# Amplificador_Push_Pull_AB.net
KiCad netlist of a schematic drawn in EAGLE
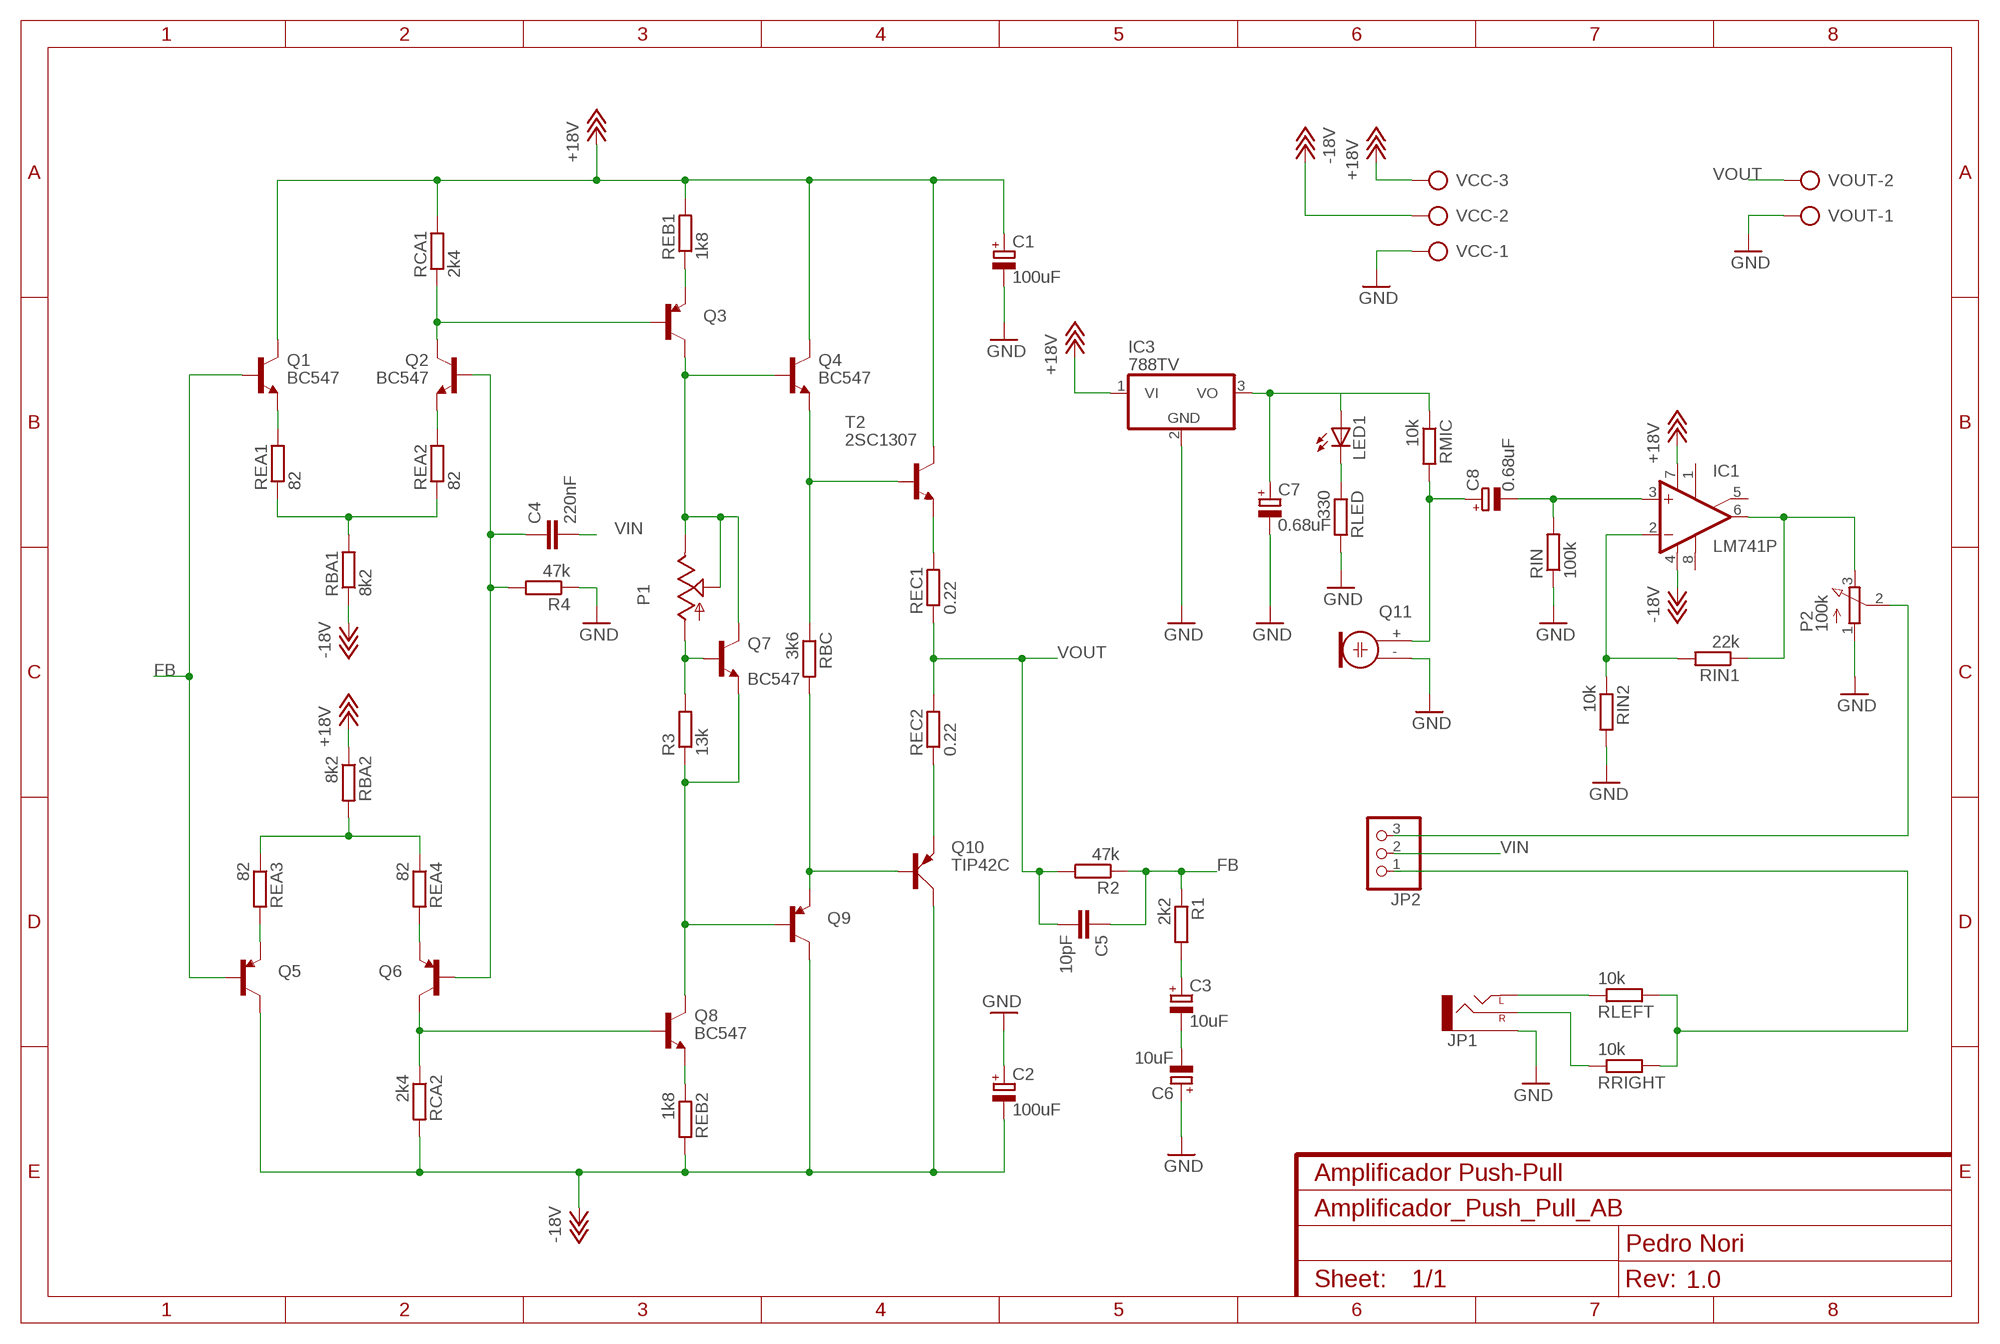
[diagram p0: schematic, sheet 1]

(export (version "E")
  (design (tool "Eeschema 10.0.6"))
  (components
    (comp (ref "C1")
      (value "100uF")
      (footprint "eagle-import:E2,5-6")
      (libsource (lib "eagle-import") (part "CPOL-EUE2.5-6"))
    )
    (comp (ref "C2")
      (value "100uF")
      (footprint "eagle-import:E2,5-6")
      (libsource (lib "eagle-import") (part "CPOL-EUE2.5-6"))
    )
    (comp (ref "C3")
      (value "10uF")
      (footprint "eagle-import:E2,5-5")
      (libsource (lib "eagle-import") (part "CPOL-EUE2.5-5"))
    )
    (comp (ref "C4")
      (value "220nF")
      (footprint "eagle-import:C025-025X050")
      (libsource (lib "eagle-import") (part "C-EU025-025X050"))
    )
    (comp (ref "C5")
      (value "10pF")
      (footprint "eagle-import:C025-025X050")
      (libsource (lib "eagle-import") (part "C-EU025-025X050"))
    )
    (comp (ref "C6")
      (value "10uF")
      (footprint "eagle-import:E2,5-5")
      (libsource (lib "eagle-import") (part "CPOL-EUE2.5-5"))
    )
    (comp (ref "C7")
      (value "0.68uF")
      (footprint "eagle-import:E2,5-5")
      (libsource (lib "eagle-import") (part "CPOL-EUE2.5-5"))
    )
    (comp (ref "C8")
      (value "0.68uF")
      (footprint "eagle-import:E2,5-5")
      (libsource (lib "eagle-import") (part "CPOL-EUE2.5-5"))
    )
    (comp (ref "IC1")
      (value "LM741P")
      (footprint "eagle-import:DIL08")
      (libsource (lib "eagle-import") (part "741PLM"))
    )
    (comp (ref "IC3")
      (value "788TV")
      (footprint "eagle-import:TO220V")
      (libsource (lib "eagle-import") (part "78TV8"))
    )
    (comp (ref "JP1")
      (value "AUDIO-JACKPTH")
      (footprint "eagle-import:AUDIO-JACK")
      (libsource (lib "eagle-import") (part "AUDIO-JACKPTH"))
    )
    (comp (ref "JP2")
      (value "PINHD-1X3")
      (footprint "eagle-import:1X03")
      (libsource (lib "eagle-import") (part "PINHD-1X3"))
    )
    (comp (ref "LED1")
      (value "LED5MM")
      (footprint "eagle-import:LED5MM")
      (libsource (lib "eagle-import") (part "LED5MM"))
    )
    (comp (ref "P1")
      (value "TRIM_US-S64W")
      (footprint "eagle-import:S64W")
      (libsource (lib "eagle-import") (part "TRIM_US-S64W"))
    )
    (comp (ref "P2")
      (value "100k")
      (footprint "eagle-import:3RP_1610N")
      (libsource (lib "eagle-import") (part "3RP/1610N"))
    )
    (comp (ref "Q1")
      (value "BC547")
      (footprint "eagle-import:TO92")
      (libsource (lib "eagle-import") (part "BC547"))
    )
    (comp (ref "Q2")
      (value "BC547")
      (footprint "eagle-import:TO92")
      (libsource (lib "eagle-import") (part "BC547"))
    )
    (comp (ref "Q3")
      (value "TRANSISTOR_PNPTO92")
      (footprint "eagle-import:TO-92")
      (libsource (lib "eagle-import") (part "TRANSISTOR_PNPTO92"))
    )
    (comp (ref "Q4")
      (value "BC547")
      (footprint "eagle-import:TO92")
      (libsource (lib "eagle-import") (part "BC547"))
    )
    (comp (ref "Q5")
      (value "TRANSISTOR_PNPTO92")
      (footprint "eagle-import:TO-92")
      (libsource (lib "eagle-import") (part "TRANSISTOR_PNPTO92"))
    )
    (comp (ref "Q6")
      (value "TRANSISTOR_PNPTO92")
      (footprint "eagle-import:TO-92")
      (libsource (lib "eagle-import") (part "TRANSISTOR_PNPTO92"))
    )
    (comp (ref "Q7")
      (value "BC547")
      (footprint "eagle-import:TO92")
      (libsource (lib "eagle-import") (part "BC547"))
    )
    (comp (ref "Q8")
      (value "BC547")
      (footprint "eagle-import:TO92")
      (libsource (lib "eagle-import") (part "BC547"))
    )
    (comp (ref "Q9")
      (value "TRANSISTOR_PNPTO92")
      (footprint "eagle-import:TO-92")
      (libsource (lib "eagle-import") (part "TRANSISTOR_PNPTO92"))
    )
    (comp (ref "Q10")
      (value "TIP42C")
      (footprint "eagle-import:TO220AV")
      (libsource (lib "eagle-import") (part "TIP42C"))
    )
    (comp (ref "Q11")
      (value "ELECTRET")
      (footprint "eagle-import:9.7ELECTRET")
      (libsource (lib "eagle-import") (part "ELECTRET"))
    )
    (comp (ref "R1")
      (value "2k2")
      (footprint "eagle-import:0207_10")
      (libsource (lib "eagle-import") (part "R-EU_0207/10"))
    )
    (comp (ref "R2")
      (value "47k")
      (footprint "eagle-import:0207_10")
      (libsource (lib "eagle-import") (part "R-EU_0207/10"))
    )
    (comp (ref "R3")
      (value "13k")
      (footprint "eagle-import:0207_10")
      (libsource (lib "eagle-import") (part "R-EU_0207/10"))
    )
    (comp (ref "R4")
      (value "47k")
      (footprint "eagle-import:0207_10")
      (libsource (lib "eagle-import") (part "R-EU_0207/10"))
    )
    (comp (ref "RBA1")
      (value "8k2")
      (footprint "eagle-import:0207_10")
      (libsource (lib "eagle-import") (part "R-EU_0207/10"))
    )
    (comp (ref "RBA2")
      (value "8k2")
      (footprint "eagle-import:0207_10")
      (libsource (lib "eagle-import") (part "R-EU_0207/10"))
    )
    (comp (ref "RBC")
      (value "3k6")
      (footprint "eagle-import:0207_10")
      (libsource (lib "eagle-import") (part "R-EU_0207/10"))
    )
    (comp (ref "RCA1")
      (value "2k4")
      (footprint "eagle-import:0207_10")
      (libsource (lib "eagle-import") (part "R-EU_0207/10"))
    )
    (comp (ref "RCA2")
      (value "2k4")
      (footprint "eagle-import:0207_10")
      (libsource (lib "eagle-import") (part "R-EU_0207/10"))
    )
    (comp (ref "REA1")
      (value "82")
      (footprint "eagle-import:0207_10")
      (libsource (lib "eagle-import") (part "R-EU_0207/10"))
    )
    (comp (ref "REA2")
      (value "82")
      (footprint "eagle-import:0207_10")
      (libsource (lib "eagle-import") (part "R-EU_0207/10"))
    )
    (comp (ref "REA3")
      (value "82")
      (footprint "eagle-import:0207_10")
      (libsource (lib "eagle-import") (part "R-EU_0207/10"))
    )
    (comp (ref "REA4")
      (value "82")
      (footprint "eagle-import:0207_10")
      (libsource (lib "eagle-import") (part "R-EU_0207/10"))
    )
    (comp (ref "REB1")
      (value "1k8")
      (footprint "eagle-import:0207_10")
      (libsource (lib "eagle-import") (part "R-EU_0207/10"))
    )
    (comp (ref "REB2")
      (value "1k8")
      (footprint "eagle-import:0207_10")
      (libsource (lib "eagle-import") (part "R-EU_0207/10"))
    )
    (comp (ref "REC1")
      (value "0.22")
      (footprint "eagle-import:0617_22")
      (libsource (lib "eagle-import") (part "R-EU_0617/22"))
    )
    (comp (ref "REC2")
      (value "0.22")
      (footprint "eagle-import:0617_22")
      (libsource (lib "eagle-import") (part "R-EU_0617/22"))
    )
    (comp (ref "RIN")
      (value "100k")
      (footprint "eagle-import:0207_7")
      (libsource (lib "eagle-import") (part "R-EU_0207/7"))
    )
    (comp (ref "RIN1")
      (value "22k")
      (footprint "eagle-import:0207_7")
      (libsource (lib "eagle-import") (part "R-EU_0207/7"))
    )
    (comp (ref "RIN2")
      (value "10k")
      (footprint "eagle-import:0207_10")
      (libsource (lib "eagle-import") (part "R-EU_0207/10"))
    )
    (comp (ref "RLED")
      (value "330")
      (footprint "eagle-import:0207_7")
      (libsource (lib "eagle-import") (part "R-EU_0207/7"))
    )
    (comp (ref "RLEFT")
      (value "10k")
      (footprint "eagle-import:0207_7")
      (libsource (lib "eagle-import") (part "R-EU_0207/7"))
    )
    (comp (ref "RMIC")
      (value "10k")
      (footprint "eagle-import:0207_7")
      (libsource (lib "eagle-import") (part "R-EU_0207/7"))
    )
    (comp (ref "RRIGHT")
      (value "10k")
      (footprint "eagle-import:0207_7")
      (libsource (lib "eagle-import") (part "R-EU_0207/7"))
    )
    (comp (ref "T2")
      (value "2SC1307")
      (footprint "eagle-import:TO220AV")
      (libsource (lib "eagle-import") (part "2SC1307"))
    )
    (comp (ref "VCC")
      (value "AK500/3-H")
      (footprint "eagle-import:AK500_3-H")
      (libsource (lib "eagle-import") (part "AK500/3-H"))
    )
    (comp (ref "VOUT")
      (value "AK500/2-H")
      (footprint "eagle-import:AK500_2-H")
      (libsource (lib "eagle-import") (part "AK500/2-H"))
    )
  )
  (nets
    (net (code "1") (name "+18V") (class "Default")
      (node (ref "C1") (pin "+") (pinfunction "+_+") (pintype "passive"))
      (node (ref "IC1") (pin "7") (pinfunction "V+_7") (pintype "power_in"))
      (node (ref "IC3") (pin "1") (pinfunction "VI_1") (pintype "input"))
      (node (ref "Q1") (pin "3") (pinfunction "C_3") (pintype "passive"))
      (node (ref "Q4") (pin "3") (pinfunction "C_3") (pintype "passive"))
      (node (ref "RBA2") (pin "1") (pinfunction "1_1") (pintype "passive"))
      (node (ref "RCA1") (pin "2") (pinfunction "2_2") (pintype "passive"))
      (node (ref "REB1") (pin "2") (pinfunction "2_2") (pintype "passive"))
      (node (ref "T2") (pin "2") (pinfunction "C_2") (pintype "passive"))
      (node (ref "VCC") (pin "3") (pinfunction "KL_3") (pintype "passive"))
    )
    (net (code "2") (name "-18V") (class "Default")
      (node (ref "C2") (pin "-") (pinfunction "-_-") (pintype "passive"))
      (node (ref "IC1") (pin "4") (pinfunction "V-_4") (pintype "power_in"))
      (node (ref "Q10") (pin "C") (pinfunction "C_C") (pintype "passive"))
      (node (ref "Q5") (pin "1") (pinfunction "C_1") (pintype "passive"))
      (node (ref "Q9") (pin "1") (pinfunction "C_1") (pintype "passive"))
      (node (ref "RBA1") (pin "1") (pinfunction "1_1") (pintype "passive"))
      (node (ref "RCA2") (pin "2") (pinfunction "2_2") (pintype "passive"))
      (node (ref "REB2") (pin "2") (pinfunction "2_2") (pintype "passive"))
      (node (ref "VCC") (pin "2") (pinfunction "KL_2") (pintype "passive"))
    )
    (net (code "3") (name "/FB") (class "Default")
      (node (ref "C5") (pin "1") (pinfunction "1_1") (pintype "passive"))
      (node (ref "Q1") (pin "2") (pinfunction "B_2") (pintype "passive"))
      (node (ref "Q5") (pin "2") (pinfunction "B_2") (pintype "passive"))
      (node (ref "R1") (pin "1") (pinfunction "1_1") (pintype "passive"))
      (node (ref "R2") (pin "1") (pinfunction "1_1") (pintype "passive"))
    )
    (net (code "4") (name "/VIN") (class "Default")
      (node (ref "C4") (pin "2") (pinfunction "2_2") (pintype "passive"))
      (node (ref "JP2") (pin "2") (pinfunction "2_2") (pintype "passive"))
    )
    (net (code "5") (name "/VOUT") (class "Default")
      (node (ref "C5") (pin "2") (pinfunction "2_2") (pintype "passive"))
      (node (ref "R2") (pin "2") (pinfunction "2_2") (pintype "passive"))
      (node (ref "REC1") (pin "1") (pinfunction "1_1") (pintype "passive"))
      (node (ref "REC2") (pin "2") (pinfunction "2_2") (pintype "passive"))
      (node (ref "VOUT") (pin "2") (pinfunction "KL_2") (pintype "passive"))
    )
    (net (code "6") (name "GND") (class "Default")
      (node (ref "C1") (pin "-") (pinfunction "-_-") (pintype "passive"))
      (node (ref "C2") (pin "+") (pinfunction "+_+") (pintype "passive"))
      (node (ref "C6") (pin "+") (pinfunction "+_+") (pintype "passive"))
      (node (ref "C7") (pin "-") (pinfunction "-_-") (pintype "passive"))
      (node (ref "IC3") (pin "2") (pinfunction "GND_2") (pintype "passive"))
      (node (ref "JP1") (pin "SLEEVE") (pinfunction "SLEEVE_SLEEVE") (pintype "bidirectional"))
      (node (ref "P2") (pin "1") (pinfunction "A_1") (pintype "passive"))
      (node (ref "Q11") (pin "-") (pinfunction "1_-") (pintype "passive"))
      (node (ref "R4") (pin "1") (pinfunction "1_1") (pintype "passive"))
      (node (ref "RIN") (pin "1") (pinfunction "1_1") (pintype "passive"))
      (node (ref "RIN2") (pin "2") (pinfunction "2_2") (pintype "passive"))
      (node (ref "RLED") (pin "2") (pinfunction "2_2") (pintype "passive"))
      (node (ref "VCC") (pin "1") (pinfunction "KL_1") (pintype "passive"))
      (node (ref "VOUT") (pin "1") (pinfunction "KL_1") (pintype "passive"))
    )
    (net (code "7") (name "Net-(C3-Pad+)") (class "Default")
      (node (ref "C3") (pin "+") (pinfunction "+_+") (pintype "passive"))
      (node (ref "R1") (pin "2") (pinfunction "2_2") (pintype "passive"))
    )
    (net (code "8") (name "Net-(C3-Pad-)") (class "Default")
      (node (ref "C3") (pin "-") (pinfunction "-_-") (pintype "passive"))
      (node (ref "C6") (pin "-") (pinfunction "-_-") (pintype "passive"))
    )
    (net (code "9") (name "Net-(IC1-+IN)") (class "Default")
      (node (ref "C8") (pin "-") (pinfunction "-_-") (pintype "passive"))
      (node (ref "IC1") (pin "3") (pinfunction "+IN_3") (pintype "input"))
      (node (ref "RIN") (pin "2") (pinfunction "2_2") (pintype "passive"))
    )
    (net (code "10") (name "Net-(IC1--IN)") (class "Default")
      (node (ref "IC1") (pin "2") (pinfunction "-IN_2") (pintype "input"))
      (node (ref "RIN1") (pin "2") (pinfunction "2_2") (pintype "passive"))
      (node (ref "RIN2") (pin "1") (pinfunction "1_1") (pintype "passive"))
    )
    (net (code "11") (name "Net-(IC1-OUT)") (class "Default")
      (node (ref "IC1") (pin "6") (pinfunction "OUT_6") (pintype "output"))
      (node (ref "P2") (pin "3") (pinfunction "E_3") (pintype "passive"))
      (node (ref "RIN1") (pin "1") (pinfunction "1_1") (pintype "passive"))
    )
    (net (code "12") (name "Net-(IC3-VO)") (class "Default")
      (node (ref "C7") (pin "+") (pinfunction "+_+") (pintype "passive"))
      (node (ref "IC3") (pin "3") (pinfunction "VO_3") (pintype "passive"))
      (node (ref "LED1") (pin "A") (pinfunction "A_A") (pintype "passive"))
      (node (ref "RMIC") (pin "1") (pinfunction "1_1") (pintype "passive"))
    )
    (net (code "13") (name "Net-(JP1-LEFT)") (class "Default")
      (node (ref "JP1") (pin "TIP") (pinfunction "LEFT_TIP") (pintype "bidirectional"))
      (node (ref "RLEFT") (pin "1") (pinfunction "1_1") (pintype "passive"))
    )
    (net (code "14") (name "Net-(JP1-RIGHT)") (class "Default")
      (node (ref "JP1") (pin "RING") (pinfunction "RIGHT_RING") (pintype "bidirectional"))
      (node (ref "RRIGHT") (pin "1") (pinfunction "1_1") (pintype "passive"))
    )
    (net (code "15") (name "Net-(JP2-Pad1)") (class "Default")
      (node (ref "JP2") (pin "1") (pinfunction "1_1") (pintype "passive"))
      (node (ref "RLEFT") (pin "2") (pinfunction "2_2") (pintype "passive"))
      (node (ref "RRIGHT") (pin "2") (pinfunction "2_2") (pintype "passive"))
    )
    (net (code "16") (name "Net-(LED1-C)") (class "Default")
      (node (ref "LED1") (pin "K") (pinfunction "C_K") (pintype "passive"))
      (node (ref "RLED") (pin "1") (pinfunction "1_1") (pintype "passive"))
    )
    (net (code "17") (name "Net-(P2-S)") (class "Default")
      (node (ref "JP2") (pin "3") (pinfunction "3_3") (pintype "passive"))
      (node (ref "P2") (pin "2") (pinfunction "S_2") (pintype "passive"))
    )
    (net (code "18") (name "Net-(Q1-E)") (class "Default")
      (node (ref "Q1") (pin "1") (pinfunction "E_1") (pintype "passive"))
      (node (ref "REA1") (pin "2") (pinfunction "2_2") (pintype "passive"))
    )
    (net (code "19") (name "Net-(Q2-B)") (class "Default")
      (node (ref "C4") (pin "1") (pinfunction "1_1") (pintype "passive"))
      (node (ref "Q2") (pin "2") (pinfunction "B_2") (pintype "passive"))
      (node (ref "Q6") (pin "2") (pinfunction "B_2") (pintype "passive"))
      (node (ref "R4") (pin "2") (pinfunction "2_2") (pintype "passive"))
    )
    (net (code "20") (name "Net-(Q2-C)") (class "Default")
      (node (ref "Q2") (pin "3") (pinfunction "C_3") (pintype "passive"))
      (node (ref "Q3") (pin "2") (pinfunction "B_2") (pintype "passive"))
      (node (ref "RCA1") (pin "1") (pinfunction "1_1") (pintype "passive"))
    )
    (net (code "21") (name "Net-(Q2-E)") (class "Default")
      (node (ref "Q2") (pin "1") (pinfunction "E_1") (pintype "passive"))
      (node (ref "REA2") (pin "2") (pinfunction "2_2") (pintype "passive"))
    )
    (net (code "22") (name "Net-(Q3-C)") (class "Default")
      (node (ref "P1") (pin "E") (pinfunction "E_E") (pintype "passive"))
      (node (ref "P1") (pin "S") (pinfunction "S_S") (pintype "passive"))
      (node (ref "Q3") (pin "1") (pinfunction "C_1") (pintype "passive"))
      (node (ref "Q4") (pin "2") (pinfunction "B_2") (pintype "passive"))
      (node (ref "Q7") (pin "3") (pinfunction "C_3") (pintype "passive"))
    )
    (net (code "23") (name "Net-(Q3-E)") (class "Default")
      (node (ref "Q3") (pin "3") (pinfunction "E_3") (pintype "passive"))
      (node (ref "REB1") (pin "1") (pinfunction "1_1") (pintype "passive"))
    )
    (net (code "24") (name "Net-(Q4-E)") (class "Default")
      (node (ref "Q4") (pin "1") (pinfunction "E_1") (pintype "passive"))
      (node (ref "RBC") (pin "1") (pinfunction "1_1") (pintype "passive"))
      (node (ref "T2") (pin "1") (pinfunction "B_1") (pintype "passive"))
    )
    (net (code "25") (name "Net-(Q5-E)") (class "Default")
      (node (ref "Q5") (pin "3") (pinfunction "E_3") (pintype "passive"))
      (node (ref "REA3") (pin "2") (pinfunction "2_2") (pintype "passive"))
    )
    (net (code "26") (name "Net-(Q6-C)") (class "Default")
      (node (ref "Q6") (pin "1") (pinfunction "C_1") (pintype "passive"))
      (node (ref "Q8") (pin "2") (pinfunction "B_2") (pintype "passive"))
      (node (ref "RCA2") (pin "1") (pinfunction "1_1") (pintype "passive"))
    )
    (net (code "27") (name "Net-(Q6-E)") (class "Default")
      (node (ref "Q6") (pin "3") (pinfunction "E_3") (pintype "passive"))
      (node (ref "REA4") (pin "2") (pinfunction "2_2") (pintype "passive"))
    )
    (net (code "28") (name "Net-(Q7-B)") (class "Default")
      (node (ref "P1") (pin "A") (pinfunction "A_A") (pintype "passive"))
      (node (ref "Q7") (pin "2") (pinfunction "B_2") (pintype "passive"))
      (node (ref "R3") (pin "2") (pinfunction "2_2") (pintype "passive"))
    )
    (net (code "29") (name "Net-(Q7-E)") (class "Default")
      (node (ref "Q7") (pin "1") (pinfunction "E_1") (pintype "passive"))
      (node (ref "Q8") (pin "3") (pinfunction "C_3") (pintype "passive"))
      (node (ref "Q9") (pin "2") (pinfunction "B_2") (pintype "passive"))
      (node (ref "R3") (pin "1") (pinfunction "1_1") (pintype "passive"))
    )
    (net (code "30") (name "Net-(Q8-E)") (class "Default")
      (node (ref "Q8") (pin "1") (pinfunction "E_1") (pintype "passive"))
      (node (ref "REB2") (pin "1") (pinfunction "1_1") (pintype "passive"))
    )
    (net (code "31") (name "Net-(Q9-E)") (class "Default")
      (node (ref "Q10") (pin "B") (pinfunction "B_B") (pintype "passive"))
      (node (ref "Q9") (pin "3") (pinfunction "E_3") (pintype "passive"))
      (node (ref "RBC") (pin "2") (pinfunction "2_2") (pintype "passive"))
    )
    (net (code "32") (name "Net-(Q10-PadE)") (class "Default")
      (node (ref "Q10") (pin "E") (pinfunction "E_E") (pintype "passive"))
      (node (ref "REC2") (pin "1") (pinfunction "1_1") (pintype "passive"))
    )
    (net (code "33") (name "Net-(Q11-2)") (class "Default")
      (node (ref "C8") (pin "+") (pinfunction "+_+") (pintype "passive"))
      (node (ref "Q11") (pin "+") (pinfunction "2_+") (pintype "passive"))
      (node (ref "RMIC") (pin "2") (pinfunction "2_2") (pintype "passive"))
    )
    (net (code "34") (name "Net-(RBA1-Pad2)") (class "Default")
      (node (ref "RBA1") (pin "2") (pinfunction "2_2") (pintype "passive"))
      (node (ref "REA1") (pin "1") (pinfunction "1_1") (pintype "passive"))
      (node (ref "REA2") (pin "1") (pinfunction "1_1") (pintype "passive"))
    )
    (net (code "35") (name "Net-(RBA2-Pad2)") (class "Default")
      (node (ref "RBA2") (pin "2") (pinfunction "2_2") (pintype "passive"))
      (node (ref "REA3") (pin "1") (pinfunction "1_1") (pintype "passive"))
      (node (ref "REA4") (pin "1") (pinfunction "1_1") (pintype "passive"))
    )
    (net (code "36") (name "Net-(T2-E)") (class "Default")
      (node (ref "REC1") (pin "2") (pinfunction "2_2") (pintype "passive"))
      (node (ref "T2") (pin "3") (pinfunction "E_3") (pintype "passive"))
    )
    (net (code "37") (name "unconnected-(IC1-ON1-Pad1)") (class "Default")
      (node (ref "IC1") (pin "1") (pinfunction "ON1_1") (pintype "passive"))
    )
    (net (code "38") (name "unconnected-(IC1-ON2-Pad5)") (class "Default")
      (node (ref "IC1") (pin "5") (pinfunction "ON2_5") (pintype "passive"))
    )
    (net (code "39") (name "unconnected-(IC1-OPT-Pad8)") (class "Default")
      (node (ref "IC1") (pin "8") (pinfunction "OPT_8") (pintype "passive"))
    )
  )
)
